# mcu.net
KiCad netlist of a schematic drawn in Altium Designer
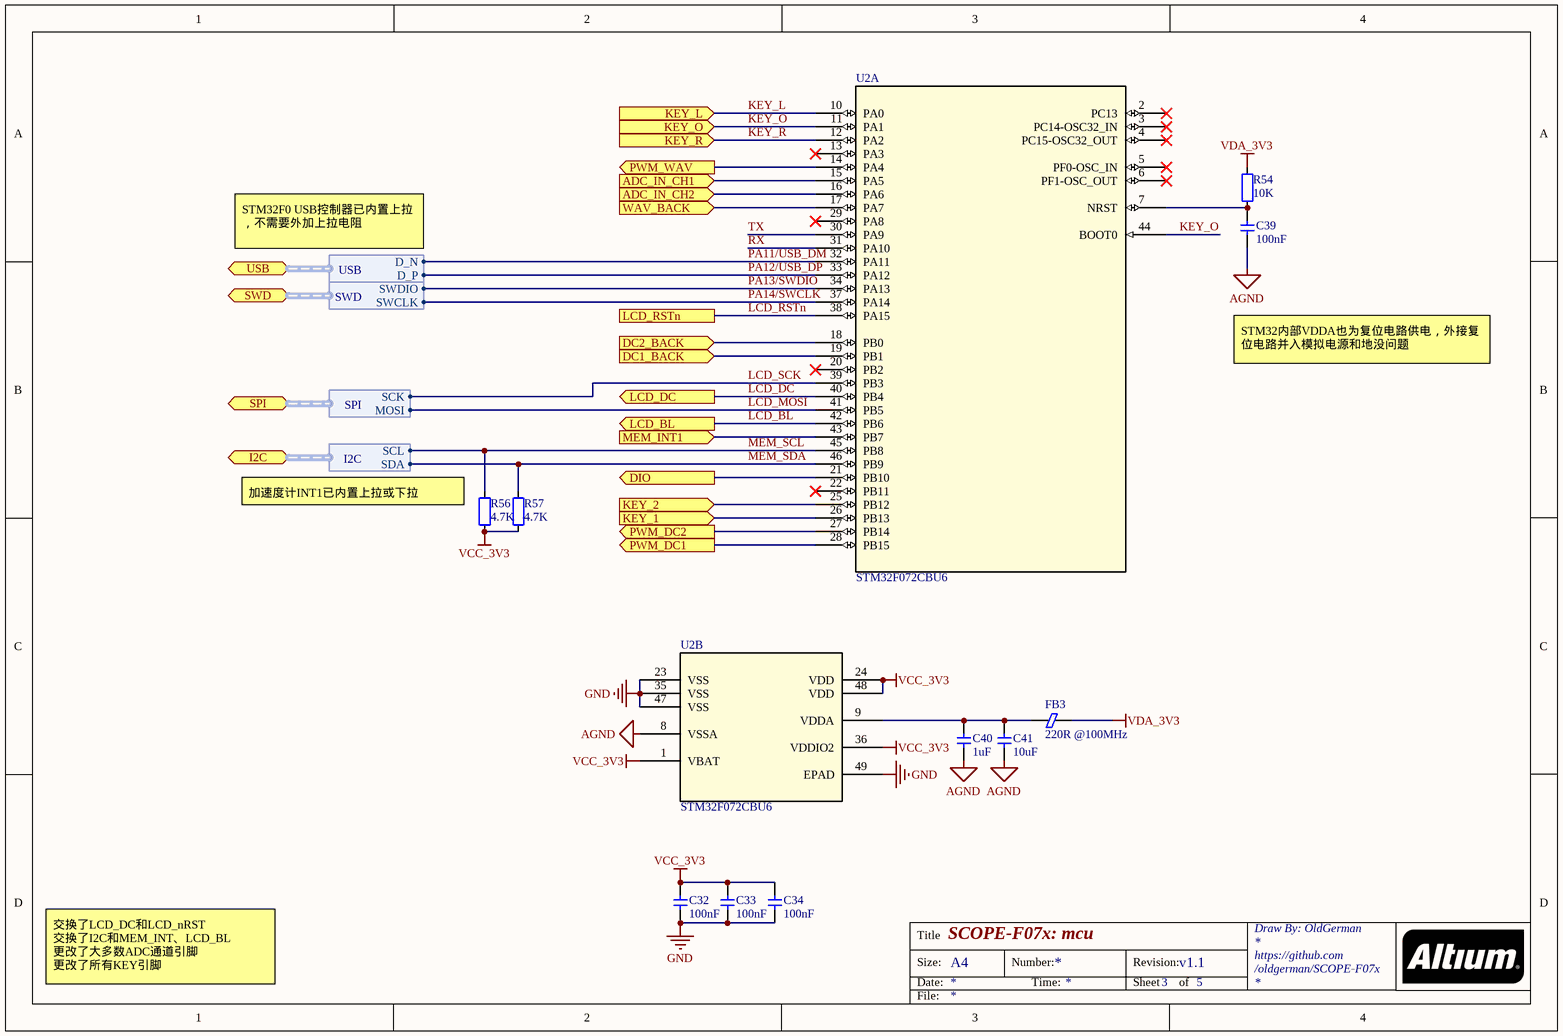
[diagram p0: mcu.SchDoc]

(export (version "E")
  (design (tool "Eeschema 10.0.6"))
  (components
    (comp (ref "C32")
      (value "100nF")
      (footprint "C0402")
      (description "Capacitor")
      (libsource (lib "ODG_AD_Lib") (part "CAP"))
    )
    (comp (ref "C33")
      (value "100nF")
      (footprint "C0402")
      (description "Capacitor")
      (libsource (lib "ODG_AD_Lib") (part "CAP"))
    )
    (comp (ref "C34")
      (value "100nF")
      (footprint "C0402")
      (description "Capacitor")
      (libsource (lib "ODG_AD_Lib") (part "CAP"))
    )
    (comp (ref "C39")
      (value "100nF")
      (footprint "C0402")
      (description "Capacitor")
      (libsource (lib "ODG_AD_Lib") (part "CAP"))
    )
    (comp (ref "C40")
      (value "1uF")
      (footprint "C0402")
      (description "Capacitor")
      (libsource (lib "ODG_AD_Lib") (part "CAP"))
    )
    (comp (ref "C41")
      (value "10uF")
      (footprint "C0402")
      (description "Capacitor")
      (libsource (lib "ODG_AD_Lib") (part "CAP"))
    )
    (comp (ref "FB3")
      (value "220R @100MHz")
      (footprint "FER0402")
      (description "磁珠")
      (libsource (lib "ODG_AD_Lib") (part "Ferrite"))
    )
    (comp (ref "R54")
      (value "10K")
      (footprint "R0402")
      (description "Resistor")
      (libsource (lib "ODG_AD_Lib") (part "RES"))
    )
    (comp (ref "R56")
      (value "4.7K")
      (footprint "R0402")
      (description "Resistor")
      (libsource (lib "") (part "RES_1"))
    )
    (comp (ref "R57")
      (value "4.7K")
      (footprint "R0402")
      (description "Resistor")
      (libsource (lib "") (part "RES_1"))
    )
    (comp (ref "U2")
      (value "STM32F072CBU6")
      (footprint "UFQFPN-48_7X7X0P55MM_VIA")
      (fields (field (name "COPYRIGHT") "Copyright (C) 2022 Ultra Librarian. All rights reserved."))
      (libsource (lib "ODG_AD_Lib") (part "STM32F072CBU6"))
    )
  )
  (nets
    (net (code "5") (name "/ADC_IN_CH1") (class "Default")
      (node (ref "U2") (pin "15") (pinfunction "PA5_15") (pintype "bidirectional"))
    )
    (net (code "6") (name "/ADC_IN_CH2") (class "Default")
      (node (ref "U2") (pin "16") (pinfunction "PA6_16") (pintype "bidirectional"))
    )
    (net (code "7") (name "/DC1_BACK") (class "Default")
      (node (ref "U2") (pin "19") (pinfunction "PB1_19") (pintype "bidirectional"))
    )
    (net (code "8") (name "/DC2_BACK") (class "Default")
      (node (ref "U2") (pin "18") (pinfunction "PB0_18") (pintype "bidirectional"))
    )
    (net (code "9") (name "/DIO") (class "Default")
      (node (ref "U2") (pin "21") (pinfunction "PB10_21") (pintype "bidirectional"))
    )
    (net (code "10") (name "/KEY_1") (class "Default")
      (node (ref "U2") (pin "26") (pinfunction "PB13_26") (pintype "bidirectional"))
    )
    (net (code "11") (name "/KEY_2") (class "Default")
      (node (ref "U2") (pin "25") (pinfunction "PB12_25") (pintype "bidirectional"))
    )
    (net (code "12") (name "/KEY_L") (class "Default")
      (node (ref "U2") (pin "10") (pinfunction "PA0_10") (pintype "bidirectional"))
    )
    (net (code "13") (name "/KEY_O") (class "Default")
      (node (ref "U2") (pin "11") (pinfunction "PA1_11") (pintype "bidirectional"))
      (node (ref "U2") (pin "44") (pinfunction "BOOT0_44") (pintype "input"))
    )
    (net (code "14") (name "/KEY_R") (class "Default")
      (node (ref "U2") (pin "12") (pinfunction "PA2_12") (pintype "bidirectional"))
    )
    (net (code "15") (name "/LCD_BL") (class "Default")
      (node (ref "U2") (pin "42") (pinfunction "PB6_42") (pintype "bidirectional"))
    )
    (net (code "16") (name "/LCD_DC") (class "Default")
      (node (ref "U2") (pin "40") (pinfunction "PB4_40") (pintype "bidirectional"))
    )
    (net (code "17") (name "/LCD_MOSI") (class "Default")
      (node (ref "U2") (pin "41") (pinfunction "PB5_41") (pintype "bidirectional"))
    )
    (net (code "18") (name "/LCD_RSTn") (class "Default")
      (node (ref "U2") (pin "38") (pinfunction "PA15_38") (pintype "bidirectional"))
    )
    (net (code "19") (name "/LCD_SCK") (class "Default")
      (node (ref "U2") (pin "39") (pinfunction "PB3_39") (pintype "bidirectional"))
    )
    (net (code "20") (name "/MEM_INT1") (class "Default")
      (node (ref "U2") (pin "43") (pinfunction "PB7_43") (pintype "bidirectional"))
    )
    (net (code "21") (name "/MEM_SCL") (class "Default")
      (node (ref "R56") (pin "2") (pinfunction "2_2") (pintype "passive"))
      (node (ref "U2") (pin "45") (pinfunction "PB8_45") (pintype "bidirectional"))
    )
    (net (code "22") (name "/MEM_SDA") (class "Default")
      (node (ref "R57") (pin "2") (pinfunction "2_2") (pintype "passive"))
      (node (ref "U2") (pin "46") (pinfunction "PB9_46") (pintype "bidirectional"))
    )
    (net (code "23") (name "/PA11{slash}USB_DM") (class "Default")
      (node (ref "U2") (pin "32") (pinfunction "PA11_32") (pintype "bidirectional"))
    )
    (net (code "24") (name "/PA12{slash}USB_DP") (class "Default")
      (node (ref "U2") (pin "33") (pinfunction "PA12_33") (pintype "bidirectional"))
    )
    (net (code "25") (name "/PA13{slash}SWDIO") (class "Default")
      (node (ref "U2") (pin "34") (pinfunction "PA13_34") (pintype "bidirectional"))
    )
    (net (code "26") (name "/PA14{slash}SWCLK") (class "Default")
      (node (ref "U2") (pin "37") (pinfunction "PA14_37") (pintype "bidirectional"))
    )
    (net (code "27") (name "/PWM_DC1") (class "Default")
      (node (ref "U2") (pin "28") (pinfunction "PB15_28") (pintype "bidirectional"))
    )
    (net (code "28") (name "/PWM_DC2") (class "Default")
      (node (ref "U2") (pin "27") (pinfunction "PB14_27") (pintype "bidirectional"))
    )
    (net (code "29") (name "/PWM_WAV") (class "Default")
      (node (ref "U2") (pin "14") (pinfunction "PA4_14") (pintype "bidirectional"))
    )
    (net (code "30") (name "/RX") (class "Default")
      (node (ref "U2") (pin "31") (pinfunction "PA10_31") (pintype "bidirectional"))
    )
    (net (code "31") (name "/TX") (class "Default")
      (node (ref "U2") (pin "30") (pinfunction "PA9_30") (pintype "bidirectional"))
    )
    (net (code "33") (name "/WAV_BACK") (class "Default")
      (node (ref "U2") (pin "17") (pinfunction "PA7_17") (pintype "bidirectional"))
    )
    (net (code "37") (name "AGND") (class "Default")
      (node (ref "C39") (pin "2") (pinfunction "2_2") (pintype "passive"))
      (node (ref "C40") (pin "2") (pinfunction "2_2") (pintype "passive"))
      (node (ref "C41") (pin "2") (pinfunction "2_2") (pintype "passive"))
      (node (ref "U2") (pin "8") (pinfunction "VSSA_8") (pintype "power_in"))
    )
    (net (code "38") (name "GND") (class "Default")
      (node (ref "C32") (pin "2") (pinfunction "2_2") (pintype "passive"))
      (node (ref "C33") (pin "2") (pinfunction "2_2") (pintype "passive"))
      (node (ref "C34") (pin "2") (pinfunction "2_2") (pintype "passive"))
      (node (ref "U2") (pin "23") (pinfunction "VSS_23") (pintype "power_in"))
      (node (ref "U2") (pin "35") (pinfunction "VSS_35") (pintype "power_in"))
      (node (ref "U2") (pin "47") (pinfunction "VSS_47") (pintype "power_in"))
      (node (ref "U2") (pin "49") (pinfunction "EPAD_49") (pintype "passive"))
    )
    (net (code "39") (name "Net-(U2A-NRST)") (class "Default")
      (node (ref "C39") (pin "1") (pinfunction "1_1") (pintype "passive"))
      (node (ref "R54") (pin "2") (pinfunction "2_2") (pintype "passive"))
      (node (ref "U2") (pin "7") (pinfunction "NRST_7") (pintype "bidirectional"))
    )
    (net (code "40") (name "Net-(U2B-VDDA)") (class "Default")
      (node (ref "C40") (pin "1") (pinfunction "1_1") (pintype "passive"))
      (node (ref "C41") (pin "1") (pinfunction "1_1") (pintype "passive"))
      (node (ref "FB3") (pin "2") (pinfunction "2_2") (pintype "passive"))
      (node (ref "U2") (pin "9") (pinfunction "VDDA_9") (pintype "power_in"))
    )
    (net (code "41") (name "VCC_3V3") (class "Default")
      (node (ref "C32") (pin "1") (pinfunction "1_1") (pintype "passive"))
      (node (ref "C33") (pin "1") (pinfunction "1_1") (pintype "passive"))
      (node (ref "C34") (pin "1") (pinfunction "1_1") (pintype "passive"))
      (node (ref "R56") (pin "1") (pinfunction "1_1") (pintype "passive"))
      (node (ref "R57") (pin "1") (pinfunction "1_1") (pintype "passive"))
      (node (ref "U2") (pin "1") (pinfunction "VBAT_1") (pintype "power_in"))
      (node (ref "U2") (pin "24") (pinfunction "VDD_24") (pintype "power_in"))
      (node (ref "U2") (pin "36") (pinfunction "VDDIO2_36") (pintype "power_in"))
      (node (ref "U2") (pin "48") (pinfunction "VDD_48") (pintype "power_in"))
    )
    (net (code "42") (name "VDA_3V3") (class "Default")
      (node (ref "FB3") (pin "1") (pinfunction "1_1") (pintype "passive"))
      (node (ref "R54") (pin "1") (pinfunction "1_1") (pintype "passive"))
    )
    (net (code "43") (name "unconnected-(U2A-PA3-Pad13)") (class "Default")
      (node (ref "U2") (pin "13") (pinfunction "PA3_13") (pintype "bidirectional+no_connect"))
    )
    (net (code "44") (name "unconnected-(U2A-PA8-Pad29)") (class "Default")
      (node (ref "U2") (pin "29") (pinfunction "PA8_29") (pintype "bidirectional+no_connect"))
    )
    (net (code "45") (name "unconnected-(U2A-PB2-Pad20)") (class "Default")
      (node (ref "U2") (pin "20") (pinfunction "PB2_20") (pintype "bidirectional+no_connect"))
    )
    (net (code "46") (name "unconnected-(U2A-PB11-Pad22)") (class "Default")
      (node (ref "U2") (pin "22") (pinfunction "PB11_22") (pintype "bidirectional+no_connect"))
    )
    (net (code "47") (name "unconnected-(U2A-PC13-Pad2)") (class "Default")
      (node (ref "U2") (pin "2") (pinfunction "PC13_2") (pintype "bidirectional+no_connect"))
    )
    (net (code "48") (name "unconnected-(U2A-PC14-OSC32_IN-Pad3)") (class "Default")
      (node (ref "U2") (pin "3") (pinfunction "PC14-OSC32_IN_3") (pintype "bidirectional+no_connect"))
    )
    (net (code "49") (name "unconnected-(U2A-PC15-OSC32_OUT-Pad4)") (class "Default")
      (node (ref "U2") (pin "4") (pinfunction "PC15-OSC32_OUT_4") (pintype "bidirectional+no_connect"))
    )
    (net (code "50") (name "unconnected-(U2A-PF0-OSC_IN-Pad5)") (class "Default")
      (node (ref "U2") (pin "5") (pinfunction "PF0-OSC_IN_5") (pintype "bidirectional+no_connect"))
    )
    (net (code "51") (name "unconnected-(U2A-PF1-OSC_OUT-Pad6)") (class "Default")
      (node (ref "U2") (pin "6") (pinfunction "PF1-OSC_OUT_6") (pintype "bidirectional+no_connect"))
    )
  )
)
